# STM32F05.net
KiCad netlist of a schematic drawn in EAGLE
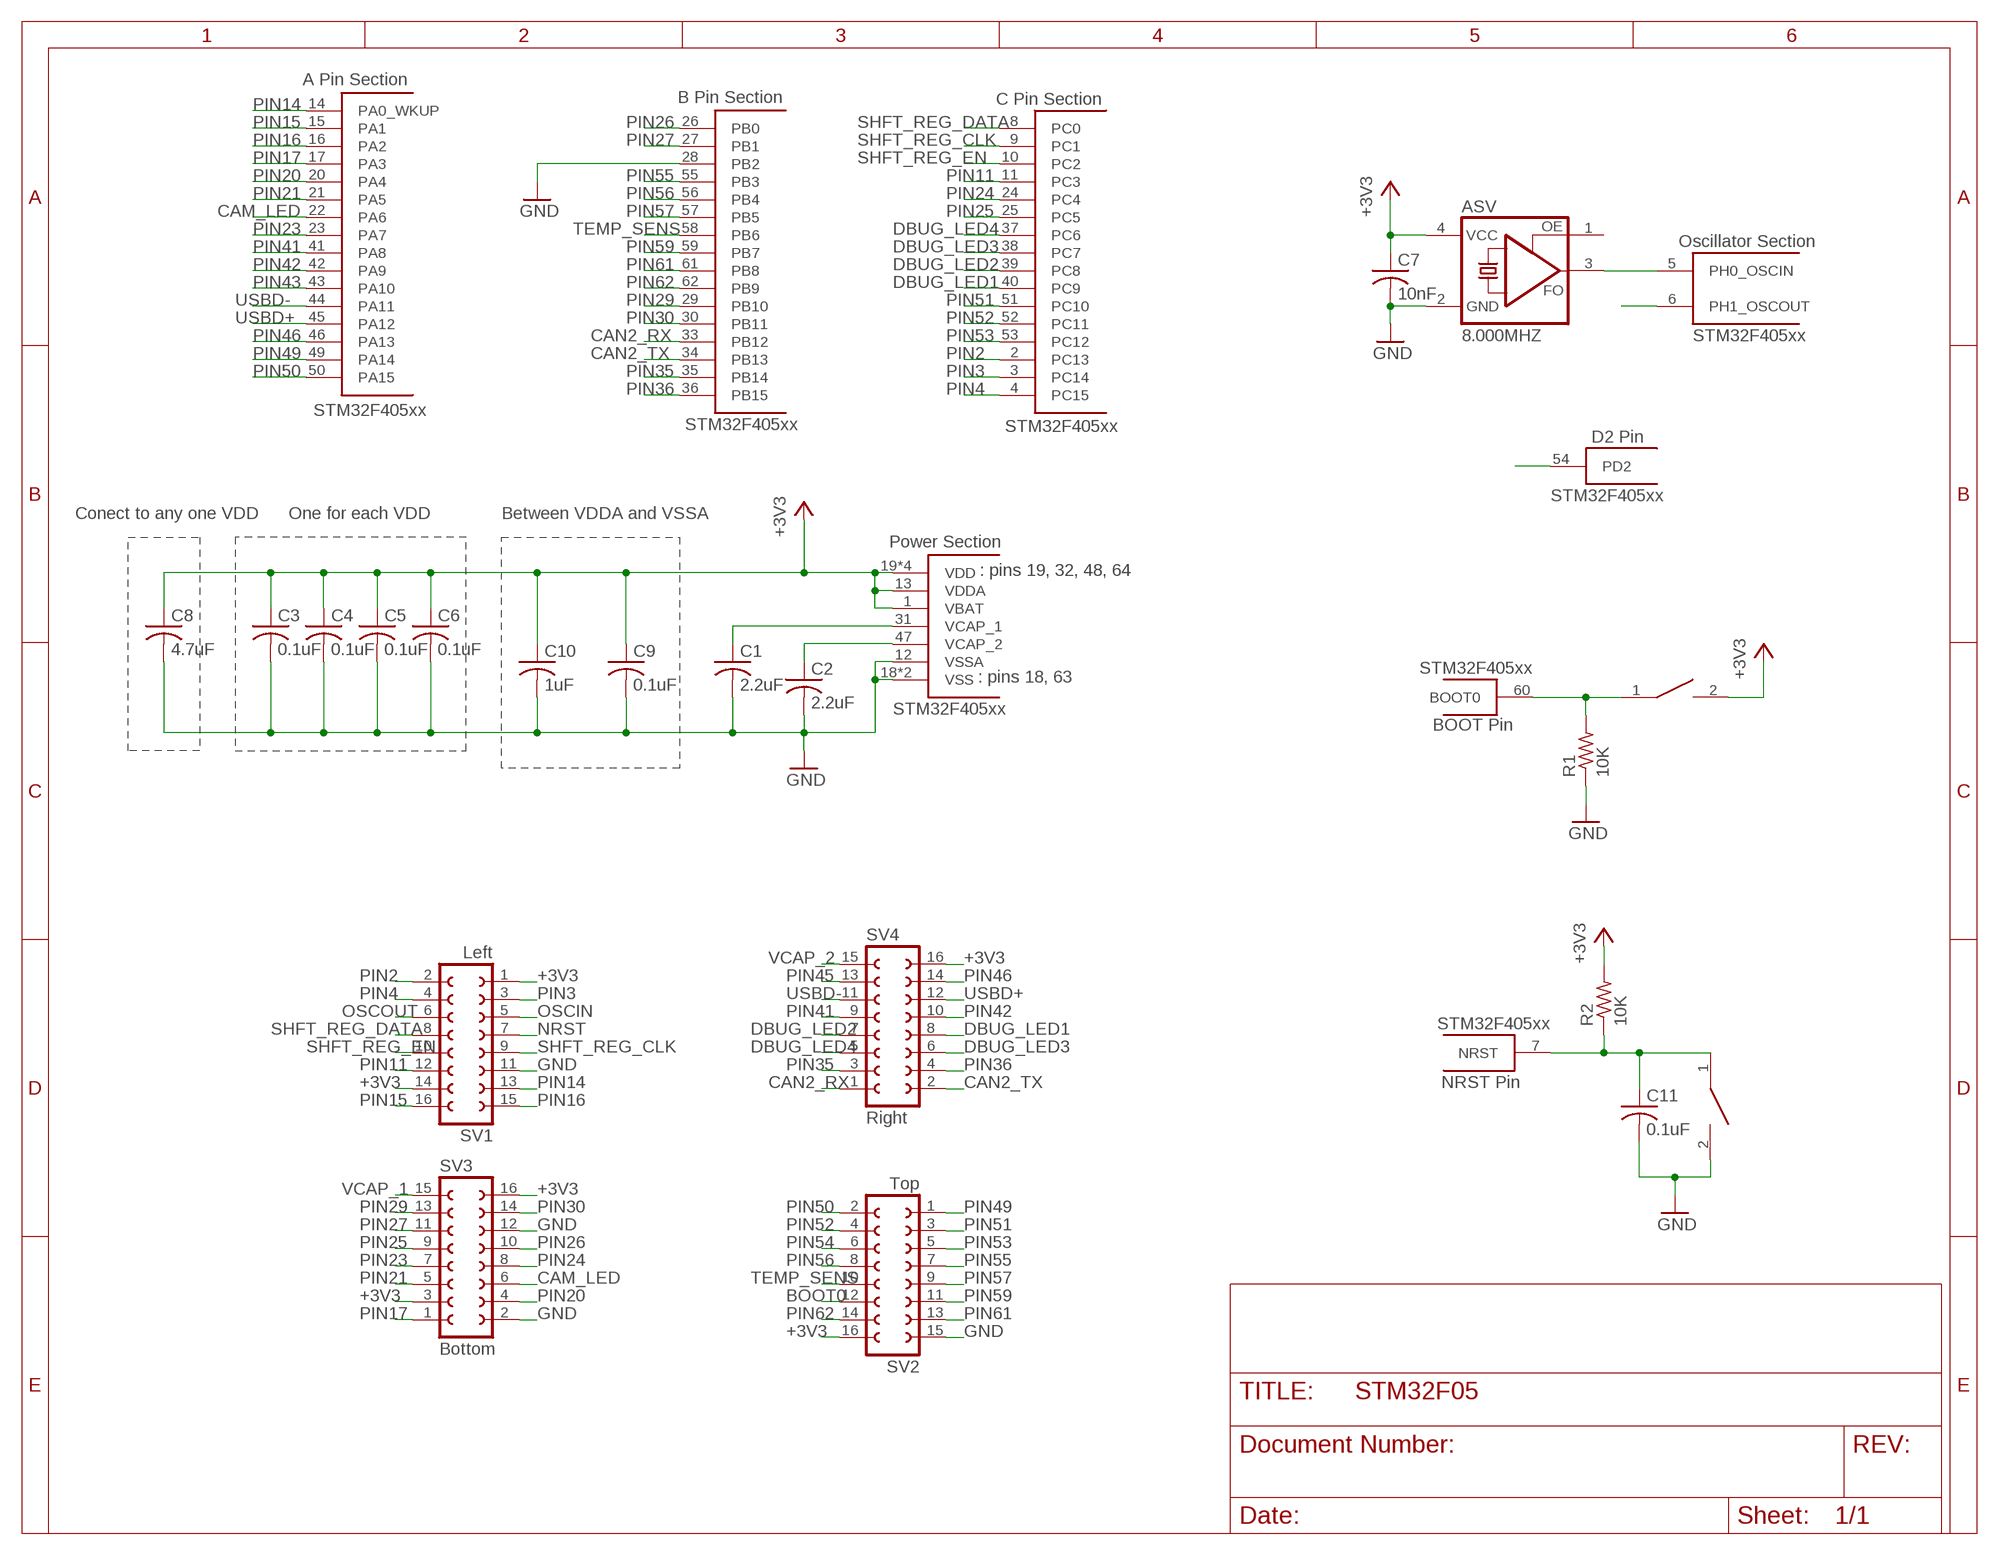
[diagram p0: schematic, sheet 1, part 1 of 2]
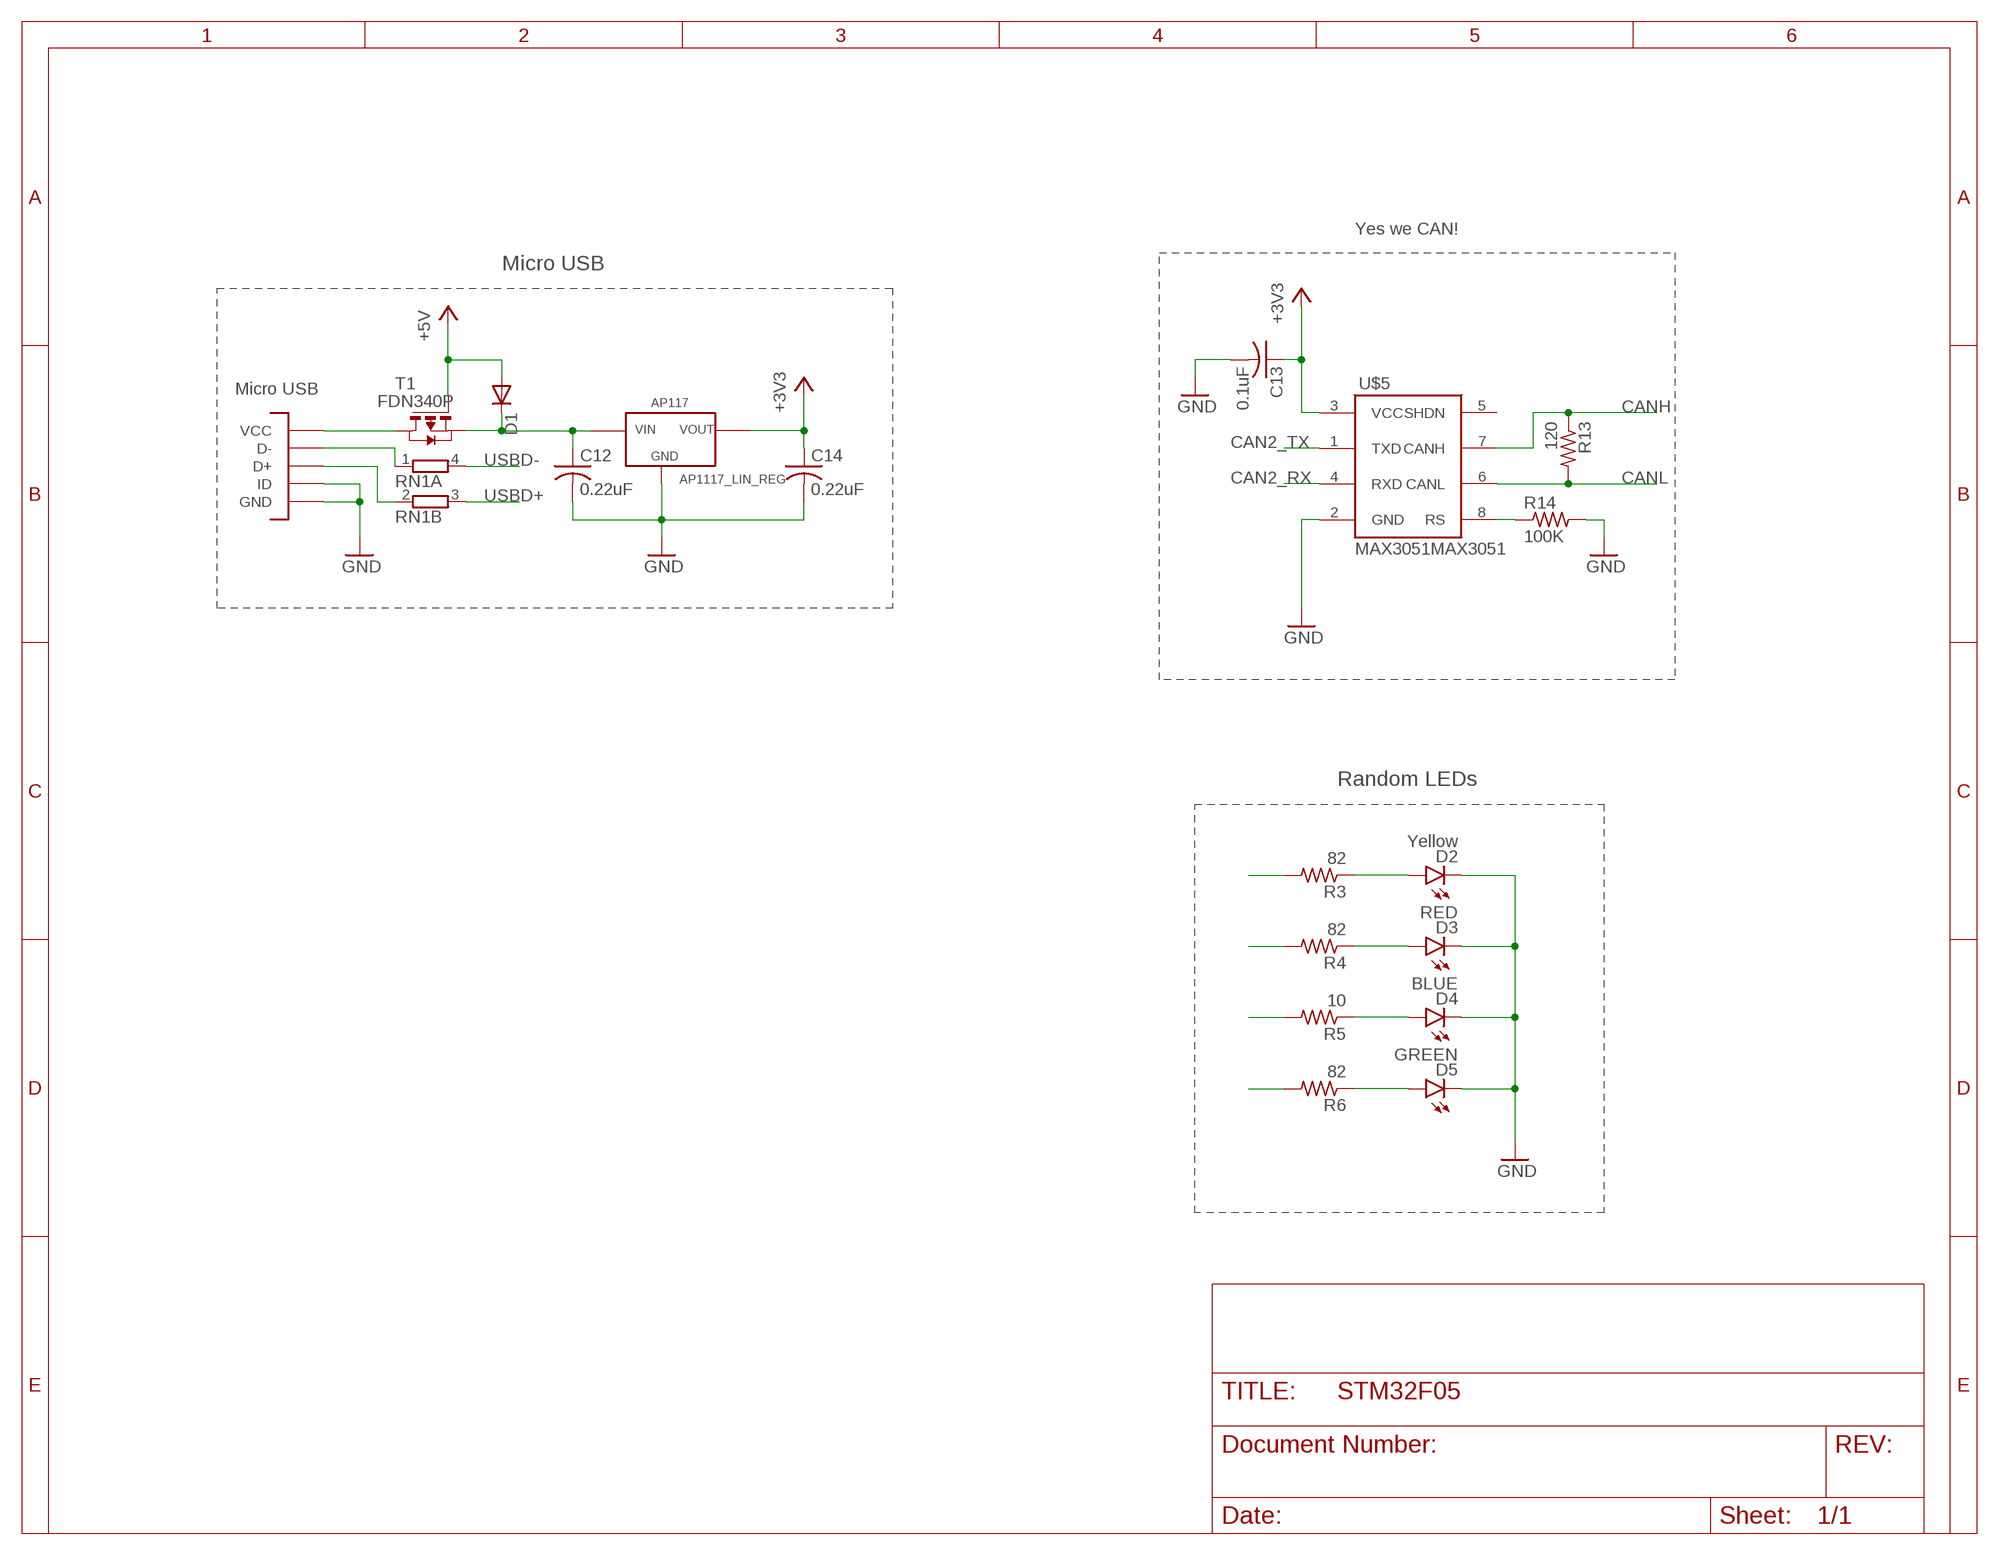
[diagram p1: schematic, sheet 1, part 2 of 2]

(export (version "E")
  (design (tool "Eeschema 10.0.6"))
  (components
    (comp (ref "ASV")
      (value "8.000MHZ")
      (footprint "eagle-import:ASF")
      (libsource (lib "eagle-import") (part "ASF"))
    )
    (comp (ref "C1")
      (value "2.2uF")
      (footprint "eagle-import:C0603")
      (libsource (lib "eagle-import") (part "C-USC0603"))
    )
    (comp (ref "C2")
      (value "2.2uF")
      (footprint "eagle-import:C0603")
      (libsource (lib "eagle-import") (part "C-USC0603"))
    )
    (comp (ref "C3")
      (value "0.1uF")
      (footprint "eagle-import:C0603")
      (libsource (lib "eagle-import") (part "C-USC0603"))
    )
    (comp (ref "C4")
      (value "0.1uF")
      (footprint "eagle-import:C0603")
      (libsource (lib "eagle-import") (part "C-USC0603"))
    )
    (comp (ref "C5")
      (value "0.1uF")
      (footprint "eagle-import:C0603")
      (libsource (lib "eagle-import") (part "C-USC0603"))
    )
    (comp (ref "C6")
      (value "0.1uF")
      (footprint "eagle-import:C0603")
      (libsource (lib "eagle-import") (part "C-USC0603"))
    )
    (comp (ref "C7")
      (value "10nF")
      (footprint "eagle-import:C0603")
      (libsource (lib "eagle-import") (part "C-USC0603"))
    )
    (comp (ref "C8")
      (value "4.7uF")
      (footprint "eagle-import:C0603")
      (libsource (lib "eagle-import") (part "C-USC0603"))
    )
    (comp (ref "C9")
      (value "0.1uF")
      (footprint "eagle-import:C0603")
      (libsource (lib "eagle-import") (part "C-USC0603"))
    )
    (comp (ref "C10")
      (value "1uF")
      (footprint "eagle-import:C0603")
      (libsource (lib "eagle-import") (part "C-USC0603"))
    )
    (comp (ref "C11")
      (value "0.1uF")
      (footprint "eagle-import:C0603")
      (libsource (lib "eagle-import") (part "C-USC0603"))
    )
    (comp (ref "C12")
      (value "0.22uF")
      (footprint "eagle-import:C0603")
      (libsource (lib "eagle-import") (part "C-USC0603"))
    )
    (comp (ref "C13")
      (value "0.1uF")
      (footprint "eagle-import:C0603")
      (libsource (lib "eagle-import") (part "C-USC0603"))
    )
    (comp (ref "C14")
      (value "0.22uF")
      (footprint "eagle-import:C0603")
      (libsource (lib "eagle-import") (part "C-USC0603"))
    )
    (comp (ref "D1")
      (value "DIODE-DO-214AC")
      (footprint "eagle-import:DO-214AC")
      (libsource (lib "eagle-import") (part "DIODE-DO-214AC"))
    )
    (comp (ref "D2")
      (value "Yellow")
      (footprint "eagle-import:LED-0603")
      (libsource (lib "eagle-import") (part "LED-YELLOW0603"))
    )
    (comp (ref "D3")
      (value "RED")
      (footprint "eagle-import:LED-0603")
      (libsource (lib "eagle-import") (part "LED-RED0603"))
    )
    (comp (ref "D4")
      (value "BLUE")
      (footprint "eagle-import:LED-0603")
      (libsource (lib "eagle-import") (part "LED-BLUE0603"))
    )
    (comp (ref "D5")
      (value "GREEN")
      (footprint "eagle-import:LED-0603")
      (libsource (lib "eagle-import") (part "LED-GREEN0603"))
    )
    (comp (ref "R1")
      (value "10K")
      (footprint "eagle-import:R0603")
      (libsource (lib "eagle-import") (part "R-US_R0603"))
    )
    (comp (ref "R2")
      (value "10K")
      (footprint "eagle-import:R0603")
      (libsource (lib "eagle-import") (part "R-US_R0603"))
    )
    (comp (ref "R3")
      (value "82")
      (footprint "eagle-import:R0603")
      (libsource (lib "eagle-import") (part "R-US_R0603"))
    )
    (comp (ref "R4")
      (value "82")
      (footprint "eagle-import:R0603")
      (libsource (lib "eagle-import") (part "R-US_R0603"))
    )
    (comp (ref "R5")
      (value "10")
      (footprint "eagle-import:R0603")
      (libsource (lib "eagle-import") (part "R-US_R0603"))
    )
    (comp (ref "R6")
      (value "82")
      (footprint "eagle-import:R0603")
      (libsource (lib "eagle-import") (part "R-US_R0603"))
    )
    (comp (ref "R13")
      (value "120")
      (footprint "eagle-import:R0603")
      (libsource (lib "eagle-import") (part "R-US_R0603"))
    )
    (comp (ref "R14")
      (value "100K")
      (footprint "eagle-import:R0603")
      (libsource (lib "eagle-import") (part "R-US_R0603"))
    )
    (comp (ref "RN1")
      (value "2R-NEXBV4V")
      (footprint "eagle-import:EXBV4V")
      (fields (field (name "MF") "Rohm Semiconductor") (field (name "MPN") "MNR12ERAPJ220"))
      (libsource (lib "eagle-import") (part "2R-NEXBV4V"))
    )
    (comp (ref "SV1")
      (value "Left")
      (footprint "eagle-import:FE08-2")
      (libsource (lib "eagle-import") (part "FE08-2"))
    )
    (comp (ref "SV2")
      (value "Top")
      (footprint "eagle-import:FE08-2")
      (libsource (lib "eagle-import") (part "FE08-2"))
    )
    (comp (ref "SV3")
      (value "Bottom")
      (footprint "eagle-import:FE08-2")
      (libsource (lib "eagle-import") (part "FE08-2"))
    )
    (comp (ref "SV4")
      (value "Right")
      (footprint "eagle-import:FE08-2")
      (libsource (lib "eagle-import") (part "FE08-2"))
    )
    (comp (ref "T1")
      (value "FDN340P")
      (footprint "eagle-import:SOT-23")
      (libsource (lib "eagle-import") (part "FDN340P"))
    )
    (comp (ref "T2")
      (value "AP1117_LIN_REG")
      (footprint "eagle-import:SOT223")
      (libsource (lib "eagle-import") (part "AP1117_LIN_REG"))
    )
    (comp (ref "U$1")
      (value "STM32F405")
      (footprint "eagle-import:LQFP64")
      (libsource (lib "eagle-import") (part "STM32F405"))
    )
    (comp (ref "U$2")
      (value "SWITCH")
      (footprint "eagle-import:SW_2512")
      (libsource (lib "eagle-import") (part "SWITCH"))
    )
    (comp (ref "U$3")
      (value "SWITCH")
      (footprint "eagle-import:SW_2512")
      (libsource (lib "eagle-import") (part "SWITCH"))
    )
    (comp (ref "U$4")
      (value "MICROUSB")
      (footprint "eagle-import:MICRO_B")
      (libsource (lib "eagle-import") (part "MICROUSB"))
    )
    (comp (ref "U$5")
      (value "MAX3051MAX3051")
      (footprint "eagle-import:SOT23-8L")
      (libsource (lib "eagle-import") (part "MAX3051MAX3051"))
    )
  )
  (nets
    (net (code "1") (name "+3V3") (class "Default")
      (node (ref "ASV") (pin "4") (pinfunction "VCC_4") (pintype "power_in"))
      (node (ref "C10") (pin "1") (pinfunction "1_1") (pintype "passive"))
      (node (ref "C13") (pin "1") (pinfunction "1_1") (pintype "passive"))
      (node (ref "C14") (pin "1") (pinfunction "1_1") (pintype "passive"))
      (node (ref "C3") (pin "1") (pinfunction "1_1") (pintype "passive"))
      (node (ref "C4") (pin "1") (pinfunction "1_1") (pintype "passive"))
      (node (ref "C5") (pin "1") (pinfunction "1_1") (pintype "passive"))
      (node (ref "C6") (pin "1") (pinfunction "1_1") (pintype "passive"))
      (node (ref "C7") (pin "1") (pinfunction "1_1") (pintype "passive"))
      (node (ref "C8") (pin "1") (pinfunction "1_1") (pintype "passive"))
      (node (ref "C9") (pin "1") (pinfunction "1_1") (pintype "passive"))
      (node (ref "R2") (pin "2") (pinfunction "2_2") (pintype "passive"))
      (node (ref "SV1") (pin "1") (pinfunction "1_1") (pintype "passive"))
      (node (ref "SV1") (pin "14") (pinfunction "14_14") (pintype "passive"))
      (node (ref "SV2") (pin "16") (pinfunction "16_16") (pintype "passive"))
      (node (ref "SV3") (pin "16") (pinfunction "16_16") (pintype "passive"))
      (node (ref "SV3") (pin "3") (pinfunction "3_3") (pintype "passive"))
      (node (ref "SV4") (pin "16") (pinfunction "16_16") (pintype "passive"))
      (node (ref "T2") (pin "TAB") (pinfunction "VOUT_TAB") (pintype "output"))
      (node (ref "T2") (pin "VOUT") (pinfunction "VOUT_VOUT") (pintype "output"))
      (node (ref "U$1") (pin "1") (pinfunction "VBAT_1") (pintype "bidirectional"))
      (node (ref "U$1") (pin "13") (pinfunction "VDDA_13") (pintype "bidirectional"))
      (node (ref "U$1") (pin "19") (pinfunction "VDD_19") (pintype "bidirectional"))
      (node (ref "U$1") (pin "32") (pinfunction "VDD_32") (pintype "bidirectional"))
      (node (ref "U$1") (pin "48") (pinfunction "VDD_48") (pintype "bidirectional"))
      (node (ref "U$1") (pin "64") (pinfunction "VDD_64") (pintype "bidirectional"))
      (node (ref "U$2") (pin "2") (pinfunction "P$2_2") (pintype "bidirectional"))
      (node (ref "U$5") (pin "3") (pinfunction "VCC_3") (pintype "bidirectional"))
    )
    (net (code "2") (name "+5V") (class "Default")
      (node (ref "D1") (pin "A") (pinfunction "A_A") (pintype "passive"))
      (node (ref "T1") (pin "3") (pinfunction "G_3") (pintype "passive"))
    )
    (net (code "3") (name "/BOOT0") (class "Default")
      (node (ref "R1") (pin "2") (pinfunction "2_2") (pintype "passive"))
      (node (ref "SV2") (pin "12") (pinfunction "12_12") (pintype "passive"))
      (node (ref "U$1") (pin "60") (pinfunction "BOOT0_60") (pintype "bidirectional"))
      (node (ref "U$2") (pin "1") (pinfunction "P$1_1") (pintype "bidirectional"))
    )
    (net (code "4") (name "/CAM_LED") (class "Default")
      (node (ref "SV3") (pin "6") (pinfunction "6_6") (pintype "passive"))
      (node (ref "U$1") (pin "22") (pinfunction "PA6_22") (pintype "bidirectional"))
    )
    (net (code "5") (name "/CAN2_RX") (class "Default")
      (node (ref "SV4") (pin "1") (pinfunction "1_1") (pintype "passive"))
      (node (ref "U$1") (pin "33") (pinfunction "PB12_33") (pintype "bidirectional"))
      (node (ref "U$5") (pin "4") (pinfunction "RXD_4") (pintype "bidirectional"))
    )
    (net (code "6") (name "/CAN2_TX") (class "Default")
      (node (ref "SV4") (pin "2") (pinfunction "2_2") (pintype "passive"))
      (node (ref "U$1") (pin "34") (pinfunction "PB13_34") (pintype "bidirectional"))
      (node (ref "U$5") (pin "1") (pinfunction "TXD_1") (pintype "bidirectional"))
    )
    (net (code "7") (name "/CANH") (class "Default")
      (node (ref "R13") (pin "1") (pinfunction "1_1") (pintype "passive"))
      (node (ref "U$5") (pin "7") (pinfunction "CANH_7") (pintype "bidirectional"))
    )
    (net (code "8") (name "/CANL") (class "Default")
      (node (ref "R13") (pin "2") (pinfunction "2_2") (pintype "passive"))
      (node (ref "U$5") (pin "6") (pinfunction "CANL_6") (pintype "bidirectional"))
    )
    (net (code "9") (name "/DBUG_LED1") (class "Default")
      (node (ref "R3") (pin "2") (pinfunction "2_2") (pintype "passive"))
      (node (ref "SV4") (pin "8") (pinfunction "8_8") (pintype "passive"))
      (node (ref "U$1") (pin "40") (pinfunction "PC9_40") (pintype "bidirectional"))
    )
    (net (code "10") (name "/DBUG_LED2") (class "Default")
      (node (ref "R4") (pin "2") (pinfunction "2_2") (pintype "passive"))
      (node (ref "SV4") (pin "7") (pinfunction "7_7") (pintype "passive"))
      (node (ref "U$1") (pin "39") (pinfunction "PC8_39") (pintype "bidirectional"))
    )
    (net (code "11") (name "/DBUG_LED3") (class "Default")
      (node (ref "R5") (pin "2") (pinfunction "2_2") (pintype "passive"))
      (node (ref "SV4") (pin "6") (pinfunction "6_6") (pintype "passive"))
      (node (ref "U$1") (pin "38") (pinfunction "PC7_38") (pintype "bidirectional"))
    )
    (net (code "12") (name "/DBUG_LED4") (class "Default")
      (node (ref "R6") (pin "2") (pinfunction "2_2") (pintype "passive"))
      (node (ref "SV4") (pin "5") (pinfunction "5_5") (pintype "passive"))
      (node (ref "U$1") (pin "37") (pinfunction "PC6_37") (pintype "bidirectional"))
    )
    (net (code "13") (name "/NRST") (class "Default")
      (node (ref "C11") (pin "1") (pinfunction "1_1") (pintype "passive"))
      (node (ref "R2") (pin "1") (pinfunction "1_1") (pintype "passive"))
      (node (ref "SV1") (pin "7") (pinfunction "7_7") (pintype "passive"))
      (node (ref "U$1") (pin "7") (pinfunction "NRST_7") (pintype "bidirectional"))
      (node (ref "U$3") (pin "1") (pinfunction "P$1_1") (pintype "bidirectional"))
    )
    (net (code "14") (name "/OSCIN") (class "Default")
      (node (ref "ASV") (pin "3") (pinfunction "FO_3") (pintype "output"))
      (node (ref "SV1") (pin "5") (pinfunction "5_5") (pintype "passive"))
      (node (ref "U$1") (pin "5") (pinfunction "PH0_OSCIN_5") (pintype "bidirectional"))
    )
    (net (code "15") (name "/OSCOUT") (class "Default")
      (node (ref "SV1") (pin "6") (pinfunction "6_6") (pintype "passive"))
      (node (ref "U$1") (pin "6") (pinfunction "PH1_OSCOUT_6") (pintype "bidirectional"))
    )
    (net (code "16") (name "/PIN2") (class "Default")
      (node (ref "SV1") (pin "2") (pinfunction "2_2") (pintype "passive"))
      (node (ref "U$1") (pin "2") (pinfunction "PC13_2") (pintype "bidirectional"))
    )
    (net (code "17") (name "/PIN3") (class "Default")
      (node (ref "SV1") (pin "3") (pinfunction "3_3") (pintype "passive"))
      (node (ref "U$1") (pin "3") (pinfunction "PC14_3") (pintype "bidirectional"))
    )
    (net (code "18") (name "/PIN4") (class "Default")
      (node (ref "SV1") (pin "4") (pinfunction "4_4") (pintype "passive"))
      (node (ref "U$1") (pin "4") (pinfunction "PC15_4") (pintype "bidirectional"))
    )
    (net (code "19") (name "/PIN11") (class "Default")
      (node (ref "SV1") (pin "12") (pinfunction "12_12") (pintype "passive"))
      (node (ref "U$1") (pin "11") (pinfunction "PC3_11") (pintype "bidirectional"))
    )
    (net (code "20") (name "/PIN14") (class "Default")
      (node (ref "SV1") (pin "13") (pinfunction "13_13") (pintype "passive"))
      (node (ref "U$1") (pin "14") (pinfunction "PA0_WKUP_14") (pintype "bidirectional"))
    )
    (net (code "21") (name "/PIN15") (class "Default")
      (node (ref "SV1") (pin "16") (pinfunction "16_16") (pintype "passive"))
      (node (ref "U$1") (pin "15") (pinfunction "PA1_15") (pintype "bidirectional"))
    )
    (net (code "22") (name "/PIN16") (class "Default")
      (node (ref "SV1") (pin "15") (pinfunction "15_15") (pintype "passive"))
      (node (ref "U$1") (pin "16") (pinfunction "PA2_16") (pintype "bidirectional"))
    )
    (net (code "23") (name "/PIN17") (class "Default")
      (node (ref "SV3") (pin "1") (pinfunction "1_1") (pintype "passive"))
      (node (ref "U$1") (pin "17") (pinfunction "PA3_17") (pintype "bidirectional"))
    )
    (net (code "24") (name "/PIN20") (class "Default")
      (node (ref "SV3") (pin "4") (pinfunction "4_4") (pintype "passive"))
      (node (ref "U$1") (pin "20") (pinfunction "PA4_20") (pintype "bidirectional"))
    )
    (net (code "25") (name "/PIN21") (class "Default")
      (node (ref "SV3") (pin "5") (pinfunction "5_5") (pintype "passive"))
      (node (ref "U$1") (pin "21") (pinfunction "PA5_21") (pintype "bidirectional"))
    )
    (net (code "26") (name "/PIN23") (class "Default")
      (node (ref "SV3") (pin "7") (pinfunction "7_7") (pintype "passive"))
      (node (ref "U$1") (pin "23") (pinfunction "PA7_23") (pintype "bidirectional"))
    )
    (net (code "27") (name "/PIN24") (class "Default")
      (node (ref "SV3") (pin "8") (pinfunction "8_8") (pintype "passive"))
      (node (ref "U$1") (pin "24") (pinfunction "PC4_24") (pintype "bidirectional"))
    )
    (net (code "28") (name "/PIN25") (class "Default")
      (node (ref "SV3") (pin "9") (pinfunction "9_9") (pintype "passive"))
      (node (ref "U$1") (pin "25") (pinfunction "PC5_25") (pintype "bidirectional"))
    )
    (net (code "29") (name "/PIN26") (class "Default")
      (node (ref "SV3") (pin "10") (pinfunction "10_10") (pintype "passive"))
      (node (ref "U$1") (pin "26") (pinfunction "PB0_26") (pintype "bidirectional"))
    )
    (net (code "30") (name "/PIN27") (class "Default")
      (node (ref "SV3") (pin "11") (pinfunction "11_11") (pintype "passive"))
      (node (ref "U$1") (pin "27") (pinfunction "PB1_27") (pintype "bidirectional"))
    )
    (net (code "31") (name "/PIN29") (class "Default")
      (node (ref "SV3") (pin "13") (pinfunction "13_13") (pintype "passive"))
      (node (ref "U$1") (pin "29") (pinfunction "PB10_29") (pintype "bidirectional"))
    )
    (net (code "32") (name "/PIN30") (class "Default")
      (node (ref "SV3") (pin "14") (pinfunction "14_14") (pintype "passive"))
      (node (ref "U$1") (pin "30") (pinfunction "PB11_30") (pintype "bidirectional"))
    )
    (net (code "33") (name "/PIN35") (class "Default")
      (node (ref "SV4") (pin "3") (pinfunction "3_3") (pintype "passive"))
      (node (ref "U$1") (pin "35") (pinfunction "PB14_35") (pintype "bidirectional"))
    )
    (net (code "34") (name "/PIN36") (class "Default")
      (node (ref "SV4") (pin "4") (pinfunction "4_4") (pintype "passive"))
      (node (ref "U$1") (pin "36") (pinfunction "PB15_36") (pintype "bidirectional"))
    )
    (net (code "35") (name "/PIN41") (class "Default")
      (node (ref "SV4") (pin "9") (pinfunction "9_9") (pintype "passive"))
      (node (ref "U$1") (pin "41") (pinfunction "PA8_41") (pintype "bidirectional"))
    )
    (net (code "36") (name "/PIN42") (class "Default")
      (node (ref "SV4") (pin "10") (pinfunction "10_10") (pintype "passive"))
      (node (ref "U$1") (pin "42") (pinfunction "PA9_42") (pintype "bidirectional"))
    )
    (net (code "37") (name "/PIN43") (class "Default")
      (node (ref "U$1") (pin "43") (pinfunction "PA10_43") (pintype "bidirectional"))
    )
    (net (code "38") (name "/PIN45") (class "Default")
      (node (ref "SV4") (pin "13") (pinfunction "13_13") (pintype "passive"))
    )
    (net (code "39") (name "/PIN46") (class "Default")
      (node (ref "SV4") (pin "14") (pinfunction "14_14") (pintype "passive"))
      (node (ref "U$1") (pin "46") (pinfunction "PA13_46") (pintype "bidirectional"))
    )
    (net (code "40") (name "/PIN49") (class "Default")
      (node (ref "SV2") (pin "1") (pinfunction "1_1") (pintype "passive"))
      (node (ref "U$1") (pin "49") (pinfunction "PA14_49") (pintype "bidirectional"))
    )
    (net (code "41") (name "/PIN50") (class "Default")
      (node (ref "SV2") (pin "2") (pinfunction "2_2") (pintype "passive"))
      (node (ref "U$1") (pin "50") (pinfunction "PA15_50") (pintype "bidirectional"))
    )
    (net (code "42") (name "/PIN51") (class "Default")
      (node (ref "SV2") (pin "3") (pinfunction "3_3") (pintype "passive"))
      (node (ref "U$1") (pin "51") (pinfunction "PC10_51") (pintype "bidirectional"))
    )
    (net (code "43") (name "/PIN52") (class "Default")
      (node (ref "SV2") (pin "4") (pinfunction "4_4") (pintype "passive"))
      (node (ref "U$1") (pin "52") (pinfunction "PC11_52") (pintype "bidirectional"))
    )
    (net (code "44") (name "/PIN53") (class "Default")
      (node (ref "SV2") (pin "5") (pinfunction "5_5") (pintype "passive"))
      (node (ref "U$1") (pin "53") (pinfunction "PC12_53") (pintype "bidirectional"))
    )
    (net (code "45") (name "/PIN54") (class "Default")
      (node (ref "SV2") (pin "6") (pinfunction "6_6") (pintype "passive"))
      (node (ref "U$1") (pin "54") (pinfunction "PD2_54") (pintype "bidirectional"))
    )
    (net (code "46") (name "/PIN55") (class "Default")
      (node (ref "SV2") (pin "7") (pinfunction "7_7") (pintype "passive"))
      (node (ref "U$1") (pin "55") (pinfunction "PB3_55") (pintype "bidirectional"))
    )
    (net (code "47") (name "/PIN56") (class "Default")
      (node (ref "SV2") (pin "8") (pinfunction "8_8") (pintype "passive"))
      (node (ref "U$1") (pin "56") (pinfunction "PB4_56") (pintype "bidirectional"))
    )
    (net (code "48") (name "/PIN57") (class "Default")
      (node (ref "SV2") (pin "9") (pinfunction "9_9") (pintype "passive"))
      (node (ref "U$1") (pin "57") (pinfunction "PB5_57") (pintype "bidirectional"))
    )
    (net (code "49") (name "/PIN59") (class "Default")
      (node (ref "SV2") (pin "11") (pinfunction "11_11") (pintype "passive"))
      (node (ref "U$1") (pin "59") (pinfunction "PB7_59") (pintype "bidirectional"))
    )
    (net (code "50") (name "/PIN61") (class "Default")
      (node (ref "SV2") (pin "13") (pinfunction "13_13") (pintype "passive"))
      (node (ref "U$1") (pin "61") (pinfunction "PB8_61") (pintype "bidirectional"))
    )
    (net (code "51") (name "/PIN62") (class "Default")
      (node (ref "SV2") (pin "14") (pinfunction "14_14") (pintype "passive"))
      (node (ref "U$1") (pin "62") (pinfunction "PB9_62") (pintype "bidirectional"))
    )
    (net (code "52") (name "/SHFT_REG_CLK") (class "Default")
      (node (ref "SV1") (pin "9") (pinfunction "9_9") (pintype "passive"))
      (node (ref "U$1") (pin "9") (pinfunction "PC1_9") (pintype "bidirectional"))
    )
    (net (code "53") (name "/SHFT_REG_DATA") (class "Default")
      (node (ref "SV1") (pin "8") (pinfunction "8_8") (pintype "passive"))
      (node (ref "U$1") (pin "8") (pinfunction "PC0_8") (pintype "bidirectional"))
    )
    (net (code "54") (name "/SHFT_REG_EN") (class "Default")
      (node (ref "SV1") (pin "10") (pinfunction "10_10") (pintype "passive"))
      (node (ref "U$1") (pin "10") (pinfunction "PC2_10") (pintype "bidirectional"))
    )
    (net (code "55") (name "/TEMP_SENS") (class "Default")
      (node (ref "SV2") (pin "10") (pinfunction "10_10") (pintype "passive"))
      (node (ref "U$1") (pin "58") (pinfunction "PB6_58") (pintype "bidirectional"))
    )
    (net (code "56") (name "/USBD+") (class "Default")
      (node (ref "RN1") (pin "3") (pinfunction "2_3") (pintype "passive"))
      (node (ref "SV4") (pin "12") (pinfunction "12_12") (pintype "passive"))
      (node (ref "U$1") (pin "45") (pinfunction "PA12_45") (pintype "bidirectional"))
    )
    (net (code "57") (name "/USBD-") (class "Default")
      (node (ref "RN1") (pin "4") (pinfunction "2_4") (pintype "passive"))
      (node (ref "SV4") (pin "11") (pinfunction "11_11") (pintype "passive"))
      (node (ref "U$1") (pin "44") (pinfunction "PA11_44") (pintype "bidirectional"))
    )
    (net (code "58") (name "/VCAP_1") (class "Default")
      (node (ref "C1") (pin "1") (pinfunction "1_1") (pintype "passive"))
      (node (ref "SV3") (pin "15") (pinfunction "15_15") (pintype "passive"))
      (node (ref "U$1") (pin "31") (pinfunction "VCAP_1_31") (pintype "bidirectional"))
    )
    (net (code "59") (name "/VCAP_2") (class "Default")
      (node (ref "C2") (pin "1") (pinfunction "1_1") (pintype "passive"))
      (node (ref "SV4") (pin "15") (pinfunction "15_15") (pintype "passive"))
      (node (ref "U$1") (pin "47") (pinfunction "VCAP_2_47") (pintype "bidirectional"))
    )
    (net (code "60") (name "GND") (class "Default")
      (node (ref "ASV") (pin "2") (pinfunction "GND_2") (pintype "power_in"))
      (node (ref "C1") (pin "2") (pinfunction "2_2") (pintype "passive"))
      (node (ref "C10") (pin "2") (pinfunction "2_2") (pintype "passive"))
      (node (ref "C11") (pin "2") (pinfunction "2_2") (pintype "passive"))
      (node (ref "C12") (pin "2") (pinfunction "2_2") (pintype "passive"))
      (node (ref "C13") (pin "2") (pinfunction "2_2") (pintype "passive"))
      (node (ref "C14") (pin "2") (pinfunction "2_2") (pintype "passive"))
      (node (ref "C2") (pin "2") (pinfunction "2_2") (pintype "passive"))
      (node (ref "C3") (pin "2") (pinfunction "2_2") (pintype "passive"))
      (node (ref "C4") (pin "2") (pinfunction "2_2") (pintype "passive"))
      (node (ref "C5") (pin "2") (pinfunction "2_2") (pintype "passive"))
      (node (ref "C6") (pin "2") (pinfunction "2_2") (pintype "passive"))
      (node (ref "C7") (pin "2") (pinfunction "2_2") (pintype "passive"))
      (node (ref "C8") (pin "2") (pinfunction "2_2") (pintype "passive"))
      (node (ref "C9") (pin "2") (pinfunction "2_2") (pintype "passive"))
      (node (ref "D2") (pin "C") (pinfunction "C_C") (pintype "passive"))
      (node (ref "D3") (pin "C") (pinfunction "C_C") (pintype "passive"))
      (node (ref "D4") (pin "C") (pinfunction "C_C") (pintype "passive"))
      (node (ref "D5") (pin "C") (pinfunction "C_C") (pintype "passive"))
      (node (ref "R1") (pin "1") (pinfunction "1_1") (pintype "passive"))
      (node (ref "R14") (pin "2") (pinfunction "2_2") (pintype "passive"))
      (node (ref "SV1") (pin "11") (pinfunction "11_11") (pintype "passive"))
      (node (ref "SV2") (pin "15") (pinfunction "15_15") (pintype "passive"))
      (node (ref "SV3") (pin "12") (pinfunction "12_12") (pintype "passive"))
      (node (ref "SV3") (pin "2") (pinfunction "2_2") (pintype "passive"))
      (node (ref "T2") (pin "GND") (pinfunction "GND_GND") (pintype "bidirectional"))
      (node (ref "U$1") (pin "12") (pinfunction "VSSA_12") (pintype "bidirectional"))
      (node (ref "U$1") (pin "18") (pinfunction "VSS_18") (pintype "bidirectional"))
      (node (ref "U$1") (pin "28") (pinfunction "PB2_28") (pintype "bidirectional"))
      (node (ref "U$1") (pin "63") (pinfunction "VSS_63") (pintype "bidirectional"))
      (node (ref "U$3") (pin "2") (pinfunction "P$2_2") (pintype "bidirectional"))
      (node (ref "U$4") (pin "GND1") (pinfunction "GND_GND1") (pintype "bidirectional"))
      (node (ref "U$4") (pin "GND2") (pinfunction "GND_GND2") (pintype "bidirectional"))
      (node (ref "U$4") (pin "GND3") (pinfunction "GND_GND3") (pintype "bidirectional"))
      (node (ref "U$4") (pin "GND4") (pinfunction "GND_GND4") (pintype "bidirectional"))
      (node (ref "U$4") (pin "GND7") (pinfunction "GND_GND7") (pintype "bidirectional"))
      (node (ref "U$4") (pin "GND8") (pinfunction "GND_GND8") (pintype "bidirectional"))
      (node (ref "U$4") (pin "P4") (pinfunction "ID_P4") (pintype "bidirectional"))
      (node (ref "U$4") (pin "P5") (pinfunction "GND_P5") (pintype "bidirectional"))
      (node (ref "U$5") (pin "2") (pinfunction "GND_2") (pintype "bidirectional"))
    )
    (net (code "61") (name "Net-(D2-PadA)") (class "Default")
      (node (ref "D2") (pin "A") (pinfunction "A_A") (pintype "passive"))
      (node (ref "R3") (pin "1") (pinfunction "1_1") (pintype "passive"))
    )
    (net (code "62") (name "Net-(D3-PadA)") (class "Default")
      (node (ref "D3") (pin "A") (pinfunction "A_A") (pintype "passive"))
      (node (ref "R4") (pin "1") (pinfunction "1_1") (pintype "passive"))
    )
    (net (code "63") (name "Net-(D4-PadA)") (class "Default")
      (node (ref "D4") (pin "A") (pinfunction "A_A") (pintype "passive"))
      (node (ref "R5") (pin "1") (pinfunction "1_1") (pintype "passive"))
    )
    (net (code "64") (name "Net-(D5-PadA)") (class "Default")
      (node (ref "D5") (pin "A") (pinfunction "A_A") (pintype "passive"))
      (node (ref "R6") (pin "1") (pinfunction "1_1") (pintype "passive"))
    )
    (net (code "65") (name "Net-(RN1B-1)") (class "Default")
      (node (ref "RN1") (pin "2") (pinfunction "1_2") (pintype "passive"))
      (node (ref "U$4") (pin "P3") (pinfunction "D+_P3") (pintype "bidirectional"))
    )
    (net (code "66") (name "Net-(T1-D)") (class "Default")
      (node (ref "T1") (pin "1") (pinfunction "D_1") (pintype "passive"))
      (node (ref "U$4") (pin "P1") (pinfunction "VCC_P1") (pintype "bidirectional"))
    )
    (net (code "67") (name "Net-(T1-S)") (class "Default")
      (node (ref "C12") (pin "1") (pinfunction "1_1") (pintype "passive"))
      (node (ref "D1") (pin "C") (pinfunction "C_C") (pintype "passive"))
      (node (ref "T1") (pin "2") (pinfunction "S_2") (pintype "passive"))
      (node (ref "T2") (pin "VIN") (pinfunction "VIN_VIN") (pintype "input"))
    )
    (net (code "68") (name "Net-(U$4-D-)") (class "Default")
      (node (ref "RN1") (pin "1") (pinfunction "1_1") (pintype "passive"))
      (node (ref "U$4") (pin "P2") (pinfunction "D-_P2") (pintype "bidirectional"))
    )
    (net (code "69") (name "Net-(U$5-RS)") (class "Default")
      (node (ref "R14") (pin "1") (pinfunction "1_1") (pintype "passive"))
      (node (ref "U$5") (pin "8") (pinfunction "RS_8") (pintype "bidirectional"))
    )
    (net (code "70") (name "unconnected-(ASV-OE-Pad1)") (class "Default")
      (node (ref "ASV") (pin "1") (pinfunction "OE_1") (pintype "input"))
    )
    (net (code "71") (name "unconnected-(U$5-SHDN-Pad5)") (class "Default")
      (node (ref "U$5") (pin "5") (pinfunction "SHDN_5") (pintype "bidirectional"))
    )
  )
)
